# v12panel.net
KiCad netlist of a schematic drawn in EAGLE
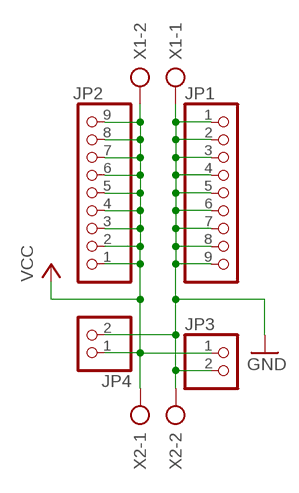
[diagram p0: schematic, sheet 1]

(export (version "E")
  (design (tool "Eeschema 10.0.6"))
  (components
    (comp (ref "JP1")
      (value "PINHD-1X9")
      (footprint "eagle-import:1X09")
      (libsource (lib "eagle-import") (part "PINHD-1X9"))
    )
    (comp (ref "JP2")
      (value "PINHD-1X9")
      (footprint "eagle-import:1X09")
      (libsource (lib "eagle-import") (part "PINHD-1X9"))
    )
    (comp (ref "JP3")
      (value "PINHD-1X2")
      (footprint "eagle-import:1X02")
      (libsource (lib "eagle-import") (part "PINHD-1X2"))
    )
    (comp (ref "JP4")
      (value "PINHD-1X2")
      (footprint "eagle-import:1X02")
      (libsource (lib "eagle-import") (part "PINHD-1X2"))
    )
    (comp (ref "X1")
      (value "AK500/2")
      (footprint "eagle-import:AK500_2")
      (libsource (lib "eagle-import") (part "AK500/2"))
    )
    (comp (ref "X2")
      (value "AK500/2")
      (footprint "eagle-import:AK500_2")
      (libsource (lib "eagle-import") (part "AK500/2"))
    )
  )
  (nets
    (net (code "1") (name "GND") (class "Default")
      (node (ref "JP1") (pin "1") (pinfunction "1_1") (pintype "passive"))
      (node (ref "JP1") (pin "2") (pinfunction "2_2") (pintype "passive"))
      (node (ref "JP1") (pin "3") (pinfunction "3_3") (pintype "passive"))
      (node (ref "JP1") (pin "4") (pinfunction "4_4") (pintype "passive"))
      (node (ref "JP1") (pin "5") (pinfunction "5_5") (pintype "passive"))
      (node (ref "JP1") (pin "6") (pinfunction "6_6") (pintype "passive"))
      (node (ref "JP1") (pin "7") (pinfunction "7_7") (pintype "passive"))
      (node (ref "JP1") (pin "8") (pinfunction "8_8") (pintype "passive"))
      (node (ref "JP1") (pin "9") (pinfunction "9_9") (pintype "passive"))
      (node (ref "JP3") (pin "2") (pinfunction "2_2") (pintype "passive"))
      (node (ref "JP4") (pin "2") (pinfunction "2_2") (pintype "passive"))
      (node (ref "X1") (pin "1") (pinfunction "KL_1") (pintype "passive"))
      (node (ref "X2") (pin "2") (pinfunction "KL_2") (pintype "passive"))
    )
    (net (code "2") (name "VCC") (class "Default")
      (node (ref "JP2") (pin "1") (pinfunction "1_1") (pintype "passive"))
      (node (ref "JP2") (pin "2") (pinfunction "2_2") (pintype "passive"))
      (node (ref "JP2") (pin "3") (pinfunction "3_3") (pintype "passive"))
      (node (ref "JP2") (pin "4") (pinfunction "4_4") (pintype "passive"))
      (node (ref "JP2") (pin "5") (pinfunction "5_5") (pintype "passive"))
      (node (ref "JP2") (pin "6") (pinfunction "6_6") (pintype "passive"))
      (node (ref "JP2") (pin "7") (pinfunction "7_7") (pintype "passive"))
      (node (ref "JP2") (pin "8") (pinfunction "8_8") (pintype "passive"))
      (node (ref "JP2") (pin "9") (pinfunction "9_9") (pintype "passive"))
      (node (ref "JP3") (pin "1") (pinfunction "1_1") (pintype "passive"))
      (node (ref "JP4") (pin "1") (pinfunction "1_1") (pintype "passive"))
      (node (ref "X1") (pin "2") (pinfunction "KL_2") (pintype "passive"))
      (node (ref "X2") (pin "1") (pinfunction "KL_1") (pintype "passive"))
    )
  )
)
